# picoAvaR10.net
KiCad netlist of a schematic drawn in EAGLE
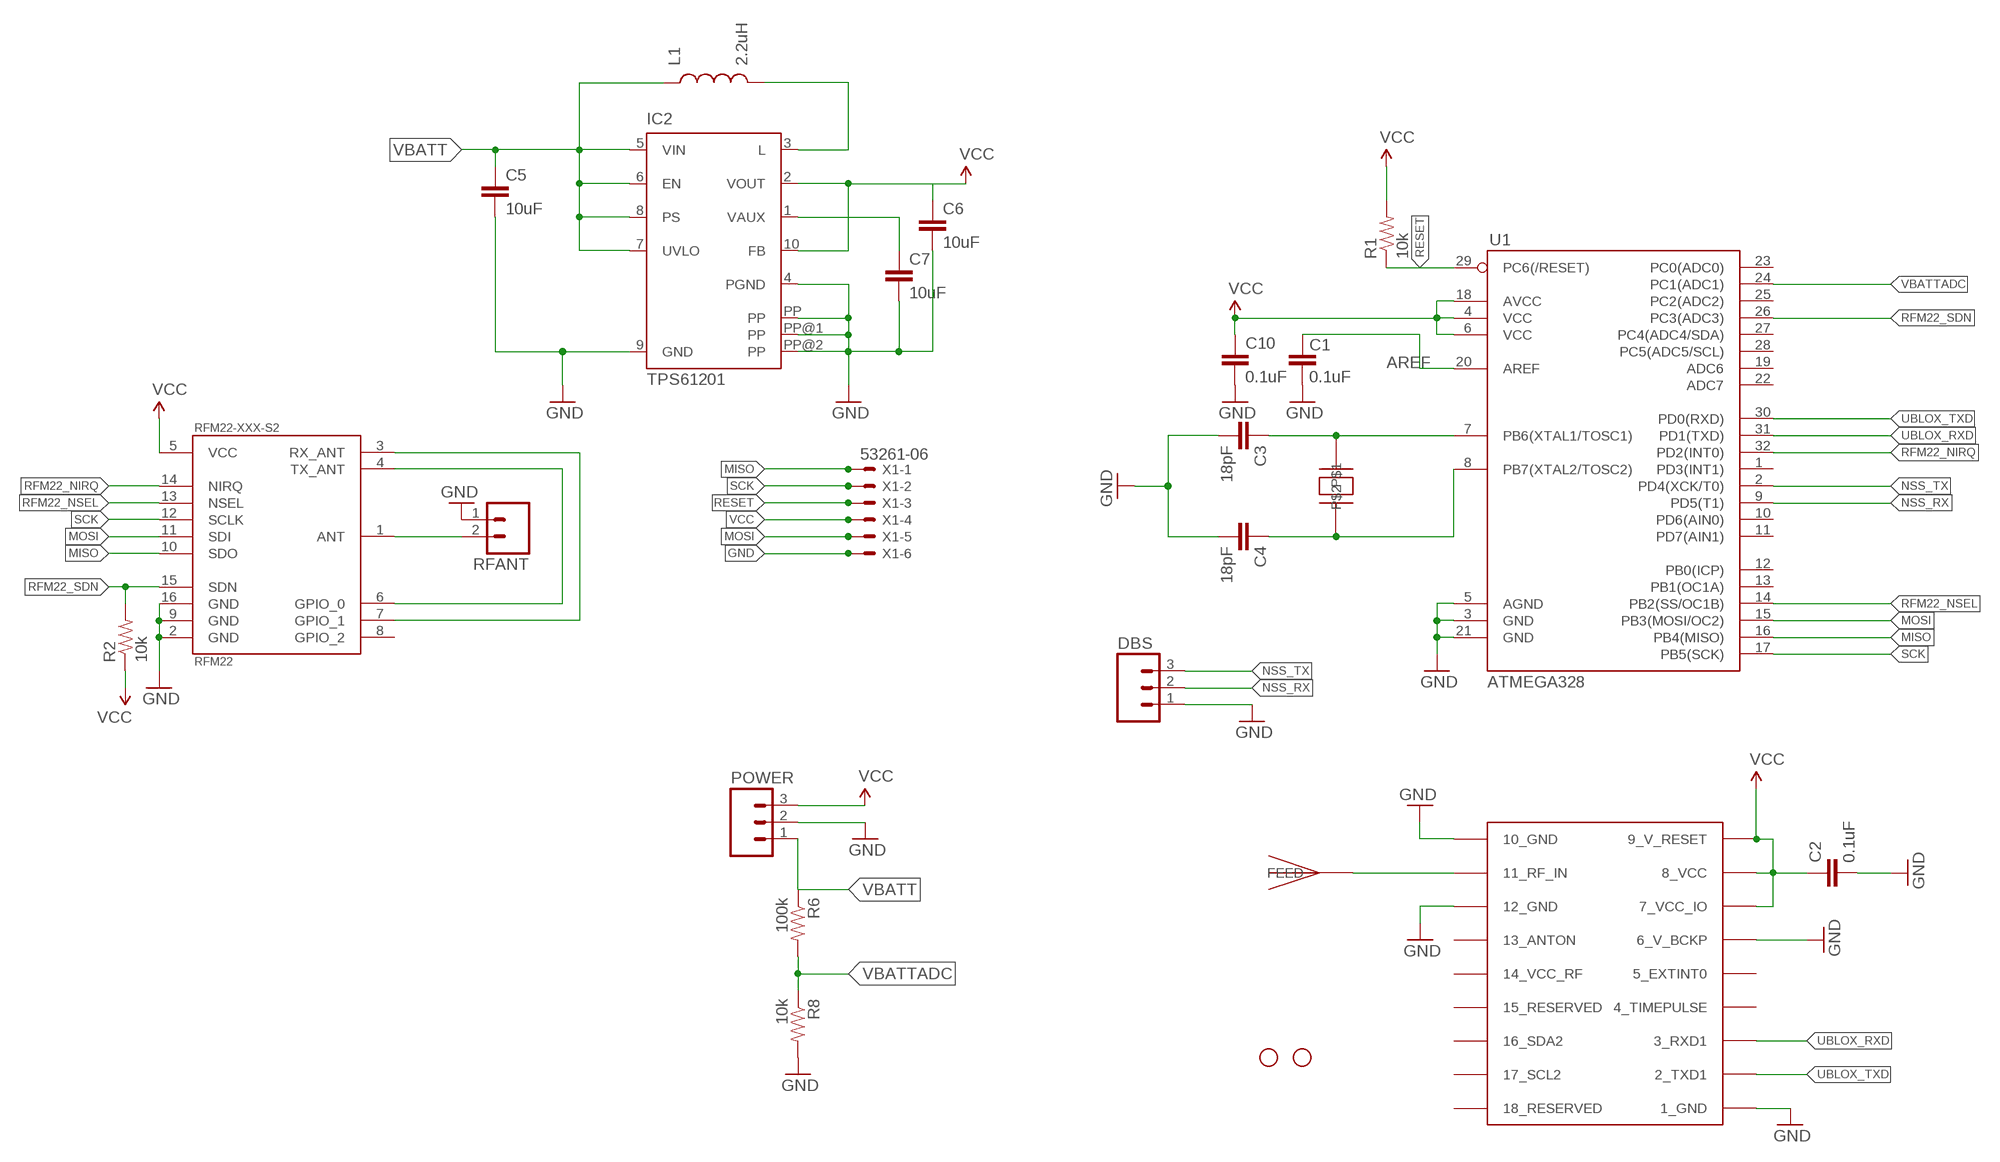
[diagram p0: schematic, sheet 1]

(export (version "E")
  (design (tool "Eeschema 10.0.6"))
  (components
    (comp (ref "C1")
      (value "0.1uF")
      (footprint "eagle-import:0402-CAP")
      (libsource (lib "eagle-import") (part "CAP0402-CAP"))
    )
    (comp (ref "C2")
      (value "0.1uF")
      (footprint "eagle-import:0402-CAP")
      (libsource (lib "eagle-import") (part "CAP0402-CAP"))
    )
    (comp (ref "C3")
      (value "18pF")
      (footprint "eagle-import:0402-CAP")
      (libsource (lib "eagle-import") (part "CAP0402-CAP"))
    )
    (comp (ref "C4")
      (value "18pF")
      (footprint "eagle-import:0402-CAP")
      (libsource (lib "eagle-import") (part "CAP0402-CAP"))
    )
    (comp (ref "C5")
      (value "10uF")
      (footprint "eagle-import:1206")
      (libsource (lib "eagle-import") (part "CAP1206"))
    )
    (comp (ref "C6")
      (value "10uF")
      (footprint "eagle-import:1206")
      (libsource (lib "eagle-import") (part "CAP1206"))
    )
    (comp (ref "C7")
      (value "10uF")
      (footprint "eagle-import:1206")
      (libsource (lib "eagle-import") (part "CAP1206"))
    )
    (comp (ref "C10")
      (value "0.1uF")
      (footprint "eagle-import:0402-CAP")
      (libsource (lib "eagle-import") (part "CAP0402-CAP"))
    )
    (comp (ref "DBS")
      (value "M03PTH")
      (footprint "eagle-import:1X03")
      (libsource (lib "eagle-import") (part "M03PTH"))
    )
    (comp (ref "IC2")
      (value "TPS61201")
      (footprint "eagle-import:S-PDSO-N10")
      (fields (field (name "MPN") "TPS61201DRCT"))
      (libsource (lib "eagle-import") (part "TPS61201"))
    )
    (comp (ref "JP1")
      (value "STAND-OFF")
      (footprint "eagle-import:STAND-OFF")
      (libsource (lib "eagle-import") (part "STAND-OFF"))
    )
    (comp (ref "JP2")
      (value "STAND-OFF")
      (footprint "eagle-import:STAND-OFF")
      (libsource (lib "eagle-import") (part "STAND-OFF"))
    )
    (comp (ref "L1")
      (value "2.2uH")
      (footprint "eagle-import:ELLVGG_INDUCTOR")
      (libsource (lib "eagle-import") (part "ELLVGG_INDUCTOR"))
    )
    (comp (ref "POWER")
      (value "M03PTH")
      (footprint "eagle-import:1X03")
      (libsource (lib "eagle-import") (part "M03PTH"))
    )
    (comp (ref "R1")
      (value "10k")
      (footprint "eagle-import:0402-RES")
      (libsource (lib "eagle-import") (part "RESISTOR0402-RES"))
    )
    (comp (ref "R2")
      (value "10k")
      (footprint "eagle-import:0402-RES")
      (libsource (lib "eagle-import") (part "RESISTOR0402-RES"))
    )
    (comp (ref "R6")
      (value "100k")
      (footprint "eagle-import:0402-RES")
      (libsource (lib "eagle-import") (part "RESISTOR0402-RES"))
    )
    (comp (ref "R8")
      (value "10k")
      (footprint "eagle-import:0402-RES")
      (libsource (lib "eagle-import") (part "RESISTOR0402-RES"))
    )
    (comp (ref "RFANT")
      (value "M02PTH")
      (footprint "eagle-import:1X02")
      (libsource (lib "eagle-import") (part "M02PTH"))
    )
    (comp (ref "RFM22-XXX-S2")
      (value "RFM22")
      (footprint "eagle-import:RFM22-XXX-S2")
      (libsource (lib "eagle-import") (part "RFM22"))
    )
    (comp (ref "U$1")
      (value "UBLOX_MAX-6")
      (footprint "eagle-import:UBLOX_MAX-6")
      (libsource (lib "eagle-import") (part "UBLOX_MAX-6"))
    )
    (comp (ref "U$2")
      (value "ABRACON_ABM3_CRYSTAL")
      (footprint "eagle-import:ABRACON_ABM3_CRYSTAL")
      (libsource (lib "eagle-import") (part "ABRACON_ABM3_CRYSTAL"))
    )
    (comp (ref "U$3")
      (value "JTI_ANTENNA-1575AT43A40")
      (footprint "eagle-import:JTI_ANTENNA-1575AT43A40")
      (libsource (lib "eagle-import") (part "JTI_ANTENNA-1575AT43A40"))
    )
    (comp (ref "U1")
      (value "ATMEGA328")
      (footprint "eagle-import:TQFP32-08")
      (libsource (lib "eagle-import") (part "ATMEGA168"))
    )
    (comp (ref "X1")
      (value "53261-06")
      (footprint "eagle-import:53261-06")
      (libsource (lib "eagle-import") (part "53?-06261"))
    )
  )
  (nets
    (net (code "1") (name "/AREF") (class "Default")
      (node (ref "C1") (pin "2") (pinfunction "2_2") (pintype "passive"))
      (node (ref "U1") (pin "20") (pinfunction "AREF_20") (pintype "bidirectional"))
    )
    (net (code "2") (name "GND") (class "Default")
      (node (ref "C1") (pin "1") (pinfunction "1_1") (pintype "passive"))
      (node (ref "C10") (pin "2") (pinfunction "2_2") (pintype "passive"))
      (node (ref "C2") (pin "2") (pinfunction "2_2") (pintype "passive"))
      (node (ref "C3") (pin "2") (pinfunction "2_2") (pintype "passive"))
      (node (ref "C4") (pin "2") (pinfunction "2_2") (pintype "passive"))
      (node (ref "C5") (pin "2") (pinfunction "2_2") (pintype "passive"))
      (node (ref "C6") (pin "2") (pinfunction "2_2") (pintype "passive"))
      (node (ref "C7") (pin "2") (pinfunction "2_2") (pintype "passive"))
      (node (ref "DBS") (pin "1") (pinfunction "1_1") (pintype "passive"))
      (node (ref "IC2") (pin "4") (pinfunction "PGND_4") (pintype "power_in"))
      (node (ref "IC2") (pin "9") (pinfunction "GND_9") (pintype "power_in"))
      (node (ref "IC2") (pin "PP") (pinfunction "PP_PP") (pintype "power_in"))
      (node (ref "IC2") (pin "PP@1") (pinfunction "PP_PP@1") (pintype "power_in"))
      (node (ref "IC2") (pin "PP@2") (pinfunction "PP_PP@2") (pintype "power_in"))
      (node (ref "POWER") (pin "2") (pinfunction "2_2") (pintype "passive"))
      (node (ref "R8") (pin "2") (pinfunction "2_2") (pintype "passive"))
      (node (ref "RFANT") (pin "1") (pinfunction "1_1") (pintype "passive"))
      (node (ref "RFM22-XXX-S2") (pin "16") (pinfunction "GND_16") (pintype "power_in"))
      (node (ref "RFM22-XXX-S2") (pin "2") (pinfunction "GND_2") (pintype "power_in"))
      (node (ref "RFM22-XXX-S2") (pin "9") (pinfunction "GND_9") (pintype "power_in"))
      (node (ref "U$1") (pin "10_GND") (pinfunction "10_GND_10_GND") (pintype "bidirectional"))
      (node (ref "U$1") (pin "12_GND") (pinfunction "12_GND_12_GND") (pintype "bidirectional"))
      (node (ref "U$1") (pin "1_GND") (pinfunction "1_GND_1_GND") (pintype "bidirectional"))
      (node (ref "U$1") (pin "6_V_BCKP") (pinfunction "6_V_BCKP_6_V_BCKP") (pintype "bidirectional"))
      (node (ref "U1") (pin "21") (pinfunction "GND_21") (pintype "bidirectional"))
      (node (ref "U1") (pin "3") (pinfunction "GND_3") (pintype "bidirectional"))
      (node (ref "U1") (pin "5") (pinfunction "AGND_5") (pintype "bidirectional"))
      (node (ref "X1") (pin "6") (pinfunction "S_6") (pintype "passive"))
    )
    (net (code "3") (name "MISO") (class "Default")
      (node (ref "RFM22-XXX-S2") (pin "10") (pinfunction "SDO_10") (pintype "output"))
      (node (ref "U1") (pin "16") (pinfunction "PB4(MISO)_16") (pintype "bidirectional"))
      (node (ref "X1") (pin "1") (pinfunction "S_1") (pintype "passive"))
    )
    (net (code "4") (name "MOSI") (class "Default")
      (node (ref "RFM22-XXX-S2") (pin "11") (pinfunction "SDI_11") (pintype "input"))
      (node (ref "U1") (pin "15") (pinfunction "PB3(MOSI/OC2)_15") (pintype "bidirectional"))
      (node (ref "X1") (pin "5") (pinfunction "S_5") (pintype "passive"))
    )
    (net (code "5") (name "NSS_RX") (class "Default")
      (node (ref "DBS") (pin "2") (pinfunction "2_2") (pintype "passive"))
      (node (ref "U1") (pin "9") (pinfunction "PD5(T1)_9") (pintype "bidirectional"))
    )
    (net (code "6") (name "NSS_TX") (class "Default")
      (node (ref "DBS") (pin "3") (pinfunction "3_3") (pintype "passive"))
      (node (ref "U1") (pin "2") (pinfunction "PD4(XCK/T0)_2") (pintype "bidirectional"))
    )
    (net (code "7") (name "Net-(IC2-L)") (class "Default")
      (node (ref "IC2") (pin "3") (pinfunction "L_3") (pintype "input"))
      (node (ref "L1") (pin "P$2") (pinfunction "2_P$2") (pintype "passive"))
    )
    (net (code "8") (name "Net-(IC2-VAUX)") (class "Default")
      (node (ref "C7") (pin "1") (pinfunction "1_1") (pintype "passive"))
      (node (ref "IC2") (pin "1") (pinfunction "VAUX_1") (pintype "bidirectional"))
    )
    (net (code "9") (name "Net-(RFM22-XXX-S2-ANT)") (class "Default")
      (node (ref "RFANT") (pin "2") (pinfunction "2_2") (pintype "passive"))
      (node (ref "RFM22-XXX-S2") (pin "1") (pinfunction "ANT_1") (pintype "bidirectional"))
    )
    (net (code "10") (name "Net-(RFM22-XXX-S2-GPIO_0)") (class "Default")
      (node (ref "RFM22-XXX-S2") (pin "4") (pinfunction "TX_ANT_4") (pintype "input"))
      (node (ref "RFM22-XXX-S2") (pin "6") (pinfunction "GPIO_0_6") (pintype "bidirectional"))
    )
    (net (code "11") (name "Net-(RFM22-XXX-S2-GPIO_1)") (class "Default")
      (node (ref "RFM22-XXX-S2") (pin "3") (pinfunction "RX_ANT_3") (pintype "input"))
      (node (ref "RFM22-XXX-S2") (pin "7") (pinfunction "GPIO_1_7") (pintype "bidirectional"))
    )
    (net (code "12") (name "Net-(U$1-Pad11_RF_IN)") (class "Default")
      (node (ref "U$1") (pin "11_RF_IN") (pinfunction "11_RF_IN_11_RF_IN") (pintype "bidirectional"))
      (node (ref "U$3") (pin "FEED") (pinfunction "FEED_FEED") (pintype "bidirectional"))
    )
    (net (code "13") (name "Net-(U1-PB6(XTAL1{slash}TOSC1))") (class "Default")
      (node (ref "C3") (pin "1") (pinfunction "1_1") (pintype "passive"))
      (node (ref "U$2") (pin "P$2") (pinfunction "P$2_P$2") (pintype "bidirectional"))
      (node (ref "U1") (pin "7") (pinfunction "PB6(XTAL1/TOSC1)_7") (pintype "bidirectional"))
    )
    (net (code "14") (name "Net-(U1-PB7(XTAL2{slash}TOSC2))") (class "Default")
      (node (ref "C4") (pin "1") (pinfunction "1_1") (pintype "passive"))
      (node (ref "U$2") (pin "P$1") (pinfunction "P$1_P$1") (pintype "bidirectional"))
      (node (ref "U1") (pin "8") (pinfunction "PB7(XTAL2/TOSC2)_8") (pintype "bidirectional"))
    )
    (net (code "15") (name "RESET") (class "Default")
      (node (ref "R1") (pin "1") (pinfunction "1_1") (pintype "passive"))
      (node (ref "U1") (pin "29") (pinfunction "PC6(/RESET)_29") (pintype "bidirectional"))
      (node (ref "X1") (pin "3") (pinfunction "S_3") (pintype "passive"))
    )
    (net (code "16") (name "RFM22_NIRQ") (class "Default")
      (node (ref "RFM22-XXX-S2") (pin "14") (pinfunction "NIRQ_14") (pintype "output"))
      (node (ref "U1") (pin "32") (pinfunction "PD2(INT0)_32") (pintype "bidirectional"))
    )
    (net (code "17") (name "RFM22_NSEL") (class "Default")
      (node (ref "RFM22-XXX-S2") (pin "13") (pinfunction "NSEL_13") (pintype "input"))
      (node (ref "U1") (pin "14") (pinfunction "PB2(SS/OC1B)_14") (pintype "bidirectional"))
    )
    (net (code "18") (name "RFM22_SDN") (class "Default")
      (node (ref "R2") (pin "2") (pinfunction "2_2") (pintype "passive"))
      (node (ref "RFM22-XXX-S2") (pin "15") (pinfunction "SDN_15") (pintype "input"))
      (node (ref "U1") (pin "26") (pinfunction "PC3(ADC3)_26") (pintype "bidirectional"))
    )
    (net (code "19") (name "SCK") (class "Default")
      (node (ref "RFM22-XXX-S2") (pin "12") (pinfunction "SCLK_12") (pintype "input"))
      (node (ref "U1") (pin "17") (pinfunction "PB5(SCK)_17") (pintype "bidirectional"))
      (node (ref "X1") (pin "2") (pinfunction "S_2") (pintype "passive"))
    )
    (net (code "20") (name "UBLOX_RXD") (class "Default")
      (node (ref "U$1") (pin "3_RXD1") (pinfunction "3_RXD1_3_RXD1") (pintype "bidirectional"))
      (node (ref "U1") (pin "31") (pinfunction "PD1(TXD)_31") (pintype "bidirectional"))
    )
    (net (code "21") (name "UBLOX_TXD") (class "Default")
      (node (ref "U$1") (pin "2_TXD1") (pinfunction "2_TXD1_2_TXD1") (pintype "bidirectional"))
      (node (ref "U1") (pin "30") (pinfunction "PD0(RXD)_30") (pintype "bidirectional"))
    )
    (net (code "22") (name "VBATT") (class "Default")
      (node (ref "C5") (pin "1") (pinfunction "1_1") (pintype "passive"))
      (node (ref "IC2") (pin "5") (pinfunction "VIN_5") (pintype "input"))
      (node (ref "IC2") (pin "6") (pinfunction "EN_6") (pintype "input"))
      (node (ref "IC2") (pin "7") (pinfunction "UVLO_7") (pintype "input"))
      (node (ref "IC2") (pin "8") (pinfunction "PS_8") (pintype "input"))
      (node (ref "L1") (pin "P$1") (pinfunction "1_P$1") (pintype "passive"))
      (node (ref "POWER") (pin "1") (pinfunction "1_1") (pintype "passive"))
      (node (ref "R6") (pin "1") (pinfunction "1_1") (pintype "passive"))
    )
    (net (code "23") (name "VBATTADC") (class "Default")
      (node (ref "R6") (pin "2") (pinfunction "2_2") (pintype "passive"))
      (node (ref "R8") (pin "1") (pinfunction "1_1") (pintype "passive"))
      (node (ref "U1") (pin "24") (pinfunction "PC1(ADC1)_24") (pintype "bidirectional"))
    )
    (net (code "24") (name "VCC") (class "Default")
      (node (ref "C10") (pin "1") (pinfunction "1_1") (pintype "passive"))
      (node (ref "C2") (pin "1") (pinfunction "1_1") (pintype "passive"))
      (node (ref "C6") (pin "1") (pinfunction "1_1") (pintype "passive"))
      (node (ref "IC2") (pin "10") (pinfunction "FB_10") (pintype "input"))
      (node (ref "IC2") (pin "2") (pinfunction "VOUT_2") (pintype "passive"))
      (node (ref "POWER") (pin "3") (pinfunction "3_3") (pintype "passive"))
      (node (ref "R1") (pin "2") (pinfunction "2_2") (pintype "passive"))
      (node (ref "R2") (pin "1") (pinfunction "1_1") (pintype "passive"))
      (node (ref "RFM22-XXX-S2") (pin "5") (pinfunction "VCC_5") (pintype "bidirectional"))
      (node (ref "U$1") (pin "7_VCC_IO") (pinfunction "7_VCC_IO_7_VCC_IO") (pintype "bidirectional"))
      (node (ref "U$1") (pin "8_VCC") (pinfunction "8_VCC_8_VCC") (pintype "bidirectional"))
      (node (ref "U$1") (pin "9_V_RESET") (pinfunction "9_V_RESET_9_V_RESET") (pintype "bidirectional"))
      (node (ref "U1") (pin "18") (pinfunction "AVCC_18") (pintype "bidirectional"))
      (node (ref "U1") (pin "4") (pinfunction "VCC_4") (pintype "bidirectional"))
      (node (ref "U1") (pin "6") (pinfunction "VCC_6") (pintype "bidirectional"))
      (node (ref "X1") (pin "4") (pinfunction "S_4") (pintype "passive"))
    )
    (net (code "25") (name "unconnected-(RFM22-XXX-S2-GPIO_2-Pad8)") (class "Default")
      (node (ref "RFM22-XXX-S2") (pin "8") (pinfunction "GPIO_2_8") (pintype "bidirectional"))
    )
    (net (code "26") (name "unconnected-(U$1-Pad4_TIMEPULSE)") (class "Default")
      (node (ref "U$1") (pin "4_TIMEPULSE") (pinfunction "4_TIMEPULSE_4_TIMEPULSE") (pintype "bidirectional"))
    )
    (net (code "27") (name "unconnected-(U$1-Pad5_EXTINT0)") (class "Default")
      (node (ref "U$1") (pin "5_EXTINT0") (pinfunction "5_EXTINT0_5_EXTINT0") (pintype "bidirectional"))
    )
    (net (code "28") (name "unconnected-(U$1-Pad13_ANTON)") (class "Default")
      (node (ref "U$1") (pin "13_ANTON") (pinfunction "13_ANTON_13_ANTON") (pintype "bidirectional"))
    )
    (net (code "29") (name "unconnected-(U$1-Pad14_VCC_RF)") (class "Default")
      (node (ref "U$1") (pin "14_VCC_RF") (pinfunction "14_VCC_RF_14_VCC_RF") (pintype "bidirectional"))
    )
    (net (code "30") (name "unconnected-(U$1-Pad15_RESERVED)") (class "Default")
      (node (ref "U$1") (pin "15_RESERVED") (pinfunction "15_RESERVED_15_RESERVED") (pintype "bidirectional"))
    )
    (net (code "31") (name "unconnected-(U$1-Pad16_SDA2)") (class "Default")
      (node (ref "U$1") (pin "16_SDA2") (pinfunction "16_SDA2_16_SDA2") (pintype "bidirectional"))
    )
    (net (code "32") (name "unconnected-(U$1-Pad17_SCL2)") (class "Default")
      (node (ref "U$1") (pin "17_SCL2") (pinfunction "17_SCL2_17_SCL2") (pintype "bidirectional"))
    )
    (net (code "33") (name "unconnected-(U$1-Pad18_RESERVED)") (class "Default")
      (node (ref "U$1") (pin "18_RESERVED") (pinfunction "18_RESERVED_18_RESERVED") (pintype "bidirectional"))
    )
    (net (code "34") (name "unconnected-(U1-ADC6-Pad19)") (class "Default")
      (node (ref "U1") (pin "19") (pinfunction "ADC6_19") (pintype "bidirectional"))
    )
    (net (code "35") (name "unconnected-(U1-ADC7-Pad22)") (class "Default")
      (node (ref "U1") (pin "22") (pinfunction "ADC7_22") (pintype "bidirectional"))
    )
    (net (code "36") (name "unconnected-(U1-PB0(ICP)-Pad12)") (class "Default")
      (node (ref "U1") (pin "12") (pinfunction "PB0(ICP)_12") (pintype "bidirectional"))
    )
    (net (code "37") (name "unconnected-(U1-PB1(OC1A)-Pad13)") (class "Default")
      (node (ref "U1") (pin "13") (pinfunction "PB1(OC1A)_13") (pintype "bidirectional"))
    )
    (net (code "38") (name "unconnected-(U1-PC0(ADC0)-Pad23)") (class "Default")
      (node (ref "U1") (pin "23") (pinfunction "PC0(ADC0)_23") (pintype "bidirectional"))
    )
    (net (code "39") (name "unconnected-(U1-PC2(ADC2)-Pad25)") (class "Default")
      (node (ref "U1") (pin "25") (pinfunction "PC2(ADC2)_25") (pintype "bidirectional"))
    )
    (net (code "40") (name "unconnected-(U1-PC4(ADC4{slash}SDA)-Pad27)") (class "Default")
      (node (ref "U1") (pin "27") (pinfunction "PC4(ADC4/SDA)_27") (pintype "bidirectional"))
    )
    (net (code "41") (name "unconnected-(U1-PC5(ADC5{slash}SCL)-Pad28)") (class "Default")
      (node (ref "U1") (pin "28") (pinfunction "PC5(ADC5/SCL)_28") (pintype "bidirectional"))
    )
    (net (code "42") (name "unconnected-(U1-PD3(INT1)-Pad1)") (class "Default")
      (node (ref "U1") (pin "1") (pinfunction "PD3(INT1)_1") (pintype "bidirectional"))
    )
    (net (code "43") (name "unconnected-(U1-PD6(AIN0)-Pad10)") (class "Default")
      (node (ref "U1") (pin "10") (pinfunction "PD6(AIN0)_10") (pintype "bidirectional"))
    )
    (net (code "44") (name "unconnected-(U1-PD7(AIN1)-Pad11)") (class "Default")
      (node (ref "U1") (pin "11") (pinfunction "PD7(AIN1)_11") (pintype "bidirectional"))
    )
  )
)
